# PDMC-S03-V00-ChannelOutput.net
KiCad netlist of a schematic drawn in Altium Designer
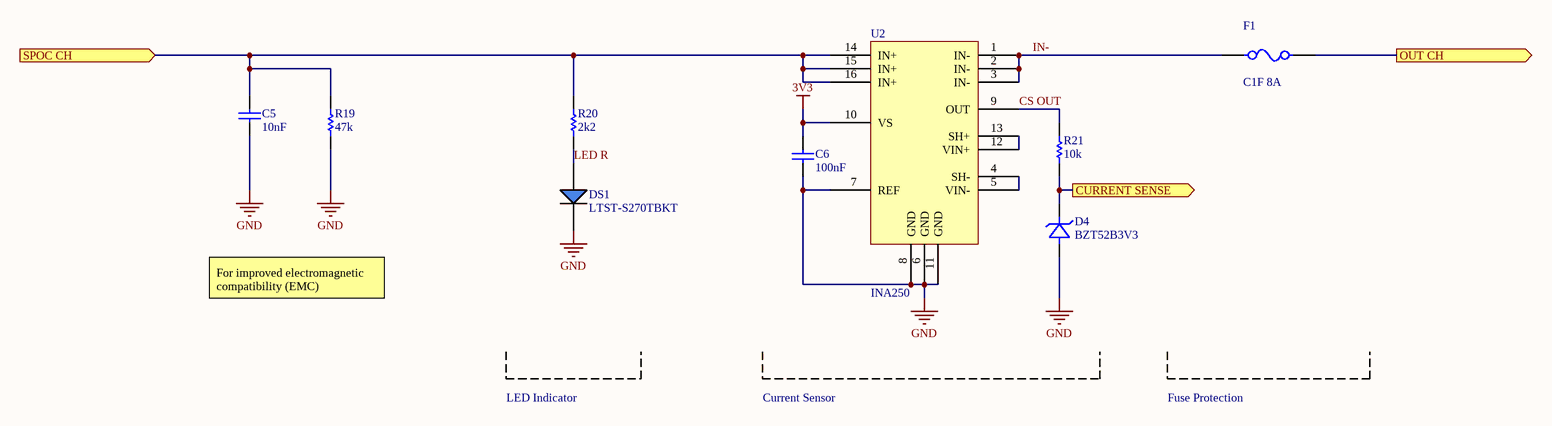
[diagram p0: PDMC-S03-V00-ChannelOutput.SchDoc]

(export (version "E")
  (design (tool "Eeschema 10.0.6"))
  (components
    (comp (ref "C5")
      (value "10nF")
      (footprint "Cap_Ceramic_0603")
      (description "Capacitor, Ceramic, SMD, 10nF, 25V, 5%, X7R, 0603")
      (libsource (lib "StandardCapacitors") (part "10nF 25V 5% X7R 0603"))
    )
    (comp (ref "C6")
      (value "100nF")
      (footprint "Cap_Ceramic_0603")
      (description "Capacitor, Ceramic, SMD, 100nF, 50V, 5%, X7R, 0603")
      (libsource (lib "StandardCapacitors") (part "100nF 50V 5% X7R 0603"))
    )
    (comp (ref "D4")
      (value "BZT52B3V3")
      (footprint "SOD123")
      (description "Diode, SMD, Zener, 3.3V, 2%, 410mW, SOD-123")
      (libsource (lib "QUTMS_DiodeLibrary") (part "BZT52B3V3"))
    )
    (comp (ref "DS1")
      (value "LTST-S270TBKT")
      (footprint "LTST-S270TBKT")
      (description "Blue 465~475nm 0603 Light Emitting Diodes (LED) RoHS")
      (libsource (lib "QUTMS_LEDLibrary") (part "LTST-S270TBKT"))
    )
    (comp (ref "F1")
      (value "C1F 8A")
      (footprint "FUSE_1206")
      (description "8A 125V AC 63V DC Fuse Board Mount (Cartridge Style Excluded) Surface Mount 1206 (3216 Metric)")
      (libsource (lib "PDM-CARD-SCHLib-V00") (part "C1F 8"))
    )
    (comp (ref "R19")
      (value "47k")
      (footprint "Res_ThinFilm_0603")
      (description "Resistor, SMD, 47k, 0.1W, 5%, 0603")
      (libsource (lib "StandardResistors") (part "47k 5% 0603"))
    )
    (comp (ref "R20")
      (value "2k2")
      (footprint "Res_ThinFilm_0603")
      (description "Resistor, SMD, 2k2, 0.1W, 5%, 0603")
      (libsource (lib "StandardResistors") (part "2k2 5% 0603"))
    )
    (comp (ref "R21")
      (value "10k")
      (footprint "Res_ThinFilm_0603")
      (description "Resistor, SMD, 10k, 0.1W, 5%, 0603")
      (libsource (lib "StandardResistors") (part "10k 5% 0603"))
    )
    (comp (ref "U2")
      (value "INA250")
      (footprint "TSSOP-16N")
      (libsource (lib "PDM-CARD-SCHLib-V00") (part "INA250"))
    )
  )
  (nets
    (net (code "1") (name "/CS OUT") (class "Default")
      (node (ref "R21") (pin "2") (pinfunction "2_2") (pintype "passive"))
      (node (ref "U2") (pin "9") (pinfunction "OUT_9") (pintype "passive"))
    )
    (net (code "2") (name "/CURRENT SENSE") (class "Default")
      (node (ref "D4") (pin "K") (pinfunction "Cathode_K") (pintype "passive"))
      (node (ref "R21") (pin "1") (pinfunction "1_1") (pintype "passive"))
    )
    (net (code "3") (name "/IN-") (class "Default")
      (node (ref "F1") (pin "1") (pinfunction "1_1") (pintype "passive"))
      (node (ref "U2") (pin "1") (pinfunction "IN-_1") (pintype "passive"))
      (node (ref "U2") (pin "2") (pinfunction "IN-_2") (pintype "passive"))
      (node (ref "U2") (pin "3") (pinfunction "IN-_3") (pintype "passive"))
    )
    (net (code "4") (name "/LED R") (class "Default")
      (node (ref "DS1") (pin "A") (pinfunction "A_A") (pintype "passive"))
      (node (ref "R20") (pin "1") (pinfunction "1_1") (pintype "passive"))
    )
    (net (code "5") (name "/OUT CH") (class "Default")
      (node (ref "F1") (pin "2") (pinfunction "2_2") (pintype "passive"))
    )
    (net (code "6") (name "/SPOC CH") (class "Default")
      (node (ref "C5") (pin "2") (pinfunction "2_2") (pintype "passive"))
      (node (ref "R19") (pin "2") (pinfunction "2_2") (pintype "passive"))
      (node (ref "R20") (pin "2") (pinfunction "2_2") (pintype "passive"))
      (node (ref "U2") (pin "14") (pinfunction "IN+_14") (pintype "passive"))
      (node (ref "U2") (pin "15") (pinfunction "IN+_15") (pintype "passive"))
      (node (ref "U2") (pin "16") (pinfunction "IN+_16") (pintype "passive"))
    )
    (net (code "7") (name "3V3") (class "Default")
      (node (ref "C6") (pin "2") (pinfunction "2_2") (pintype "passive"))
      (node (ref "U2") (pin "10") (pinfunction "VS_10") (pintype "passive"))
    )
    (net (code "8") (name "GND") (class "Default")
      (node (ref "C5") (pin "1") (pinfunction "1_1") (pintype "passive"))
      (node (ref "C6") (pin "1") (pinfunction "1_1") (pintype "passive"))
      (node (ref "D4") (pin "A") (pinfunction "Anode_A") (pintype "passive"))
      (node (ref "DS1") (pin "K") (pinfunction "K_K") (pintype "passive"))
      (node (ref "R19") (pin "1") (pinfunction "1_1") (pintype "passive"))
      (node (ref "U2") (pin "11") (pinfunction "GND_11") (pintype "passive"))
      (node (ref "U2") (pin "6") (pinfunction "GND_6") (pintype "passive"))
      (node (ref "U2") (pin "7") (pinfunction "REF_7") (pintype "passive"))
      (node (ref "U2") (pin "8") (pinfunction "GND_8") (pintype "passive"))
    )
    (net (code "9") (name "Net-(U2-SH+)") (class "Default")
      (node (ref "U2") (pin "12") (pinfunction "VIN+_12") (pintype "passive"))
      (node (ref "U2") (pin "13") (pinfunction "SH+_13") (pintype "passive"))
    )
    (net (code "10") (name "Net-(U2-SH-)") (class "Default")
      (node (ref "U2") (pin "4") (pinfunction "SH-_4") (pintype "passive"))
      (node (ref "U2") (pin "5") (pinfunction "VIN-_5") (pintype "passive"))
    )
  )
)
